# OSO-SAFE-C1-02.net
KiCad netlist of a schematic drawn in EAGLE
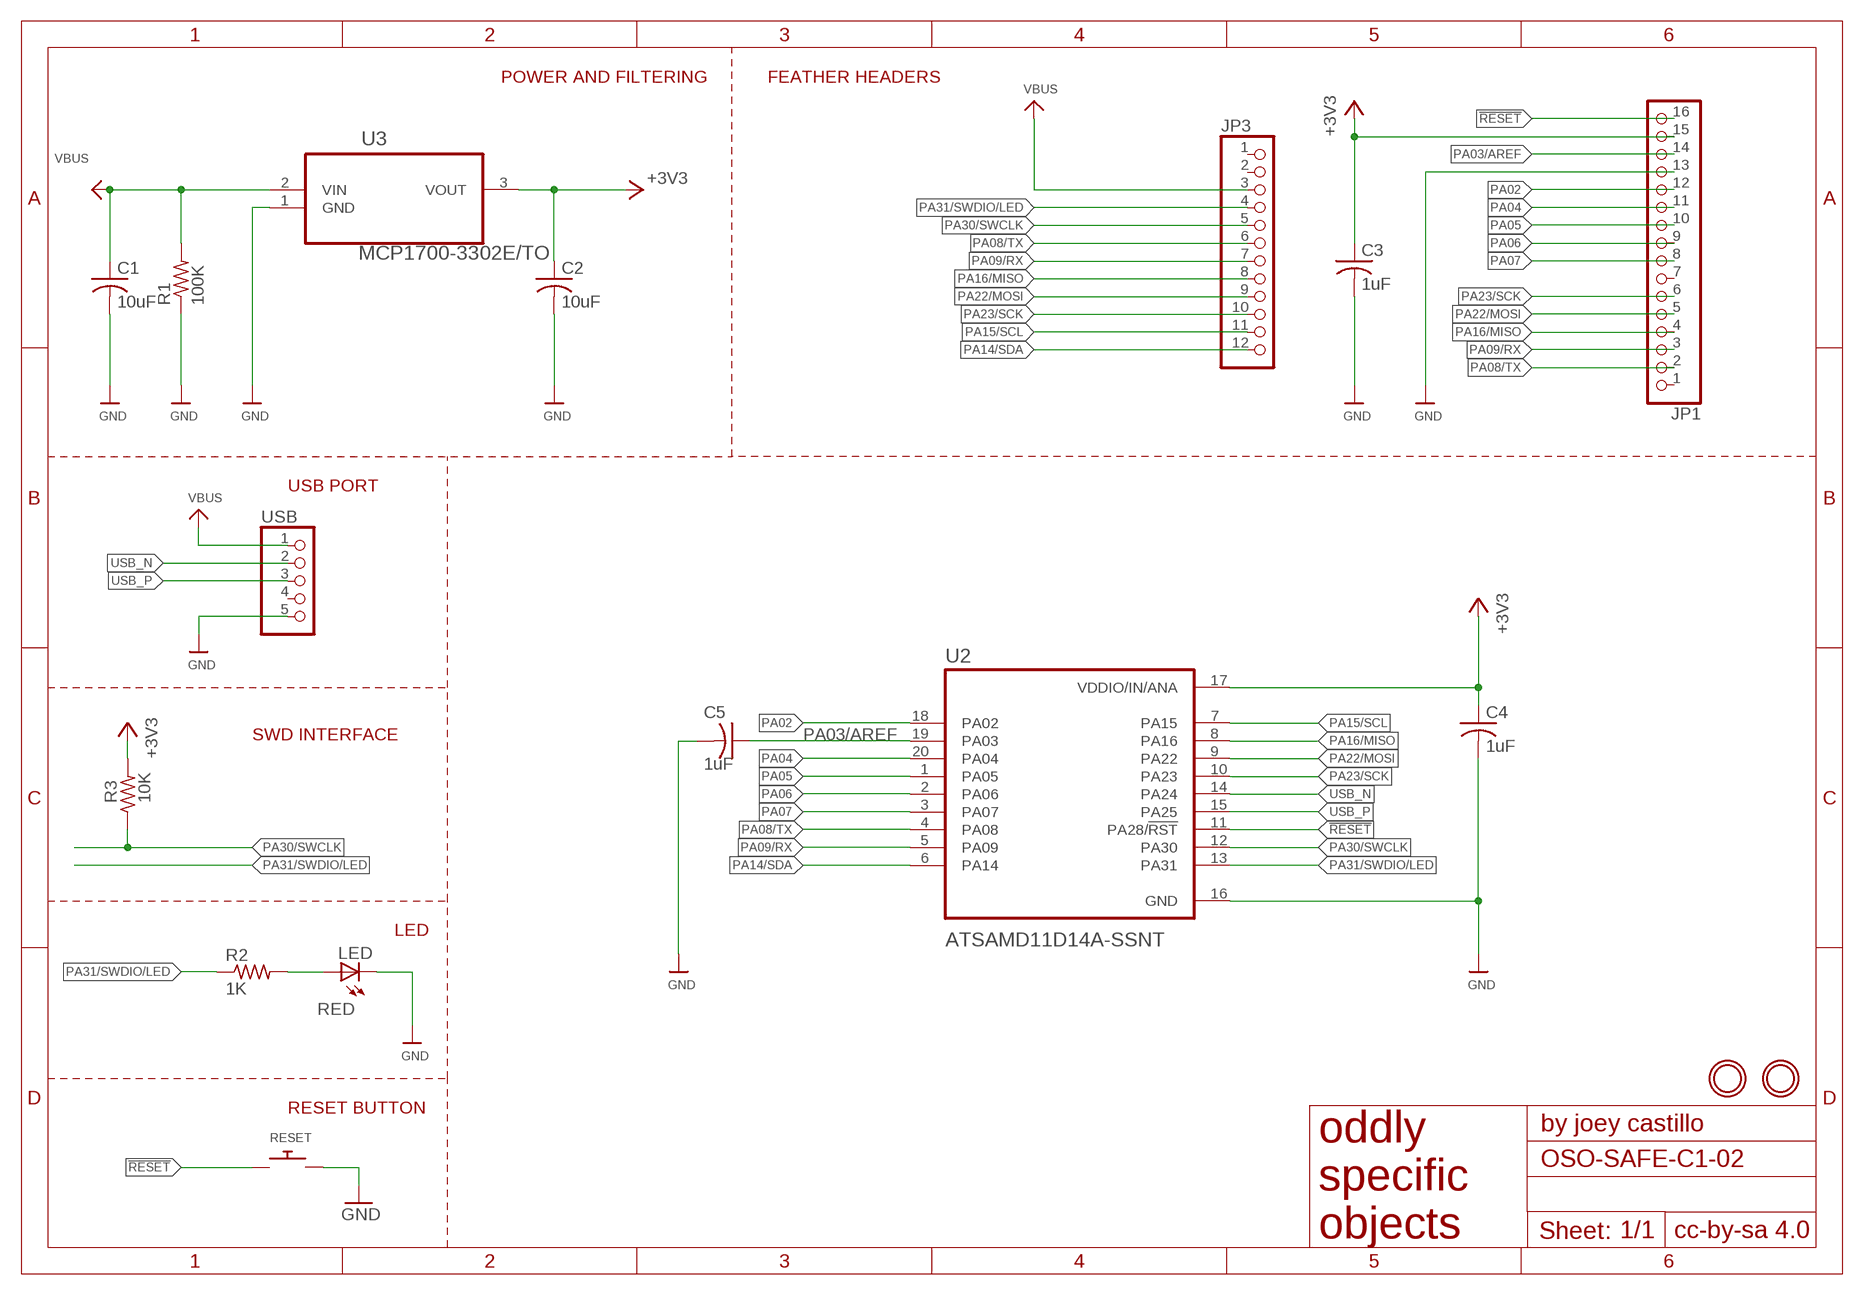
[diagram p0: schematic, sheet 1]

(export (version "E")
  (design (tool "Eeschema 10.0.6"))
  (components
    (comp (ref "C1")
      (value "10uF")
      (footprint "eagle-import:C050-025X075")
      (libsource (lib "eagle-import") (part "C-US050-025X075"))
    )
    (comp (ref "C2")
      (value "10uF")
      (footprint "eagle-import:C050-025X075")
      (libsource (lib "eagle-import") (part "C-US050-025X075"))
    )
    (comp (ref "C3")
      (value "1uF")
      (footprint "eagle-import:C025-025X050")
      (libsource (lib "eagle-import") (part "C-US025-025X050"))
    )
    (comp (ref "C4")
      (value "1uF")
      (footprint "eagle-import:C025-025X050")
      (libsource (lib "eagle-import") (part "C-US025-025X050"))
    )
    (comp (ref "C5")
      (value "1uF")
      (footprint "eagle-import:C025-025X050")
      (libsource (lib "eagle-import") (part "C-US025-025X050"))
    )
    (comp (ref "JP1")
      (value "HEADER-1X16_MIN")
      (footprint "eagle-import:1X16_ROUND_MIN")
      (libsource (lib "eagle-import") (part "HEADER-1X16_MIN"))
    )
    (comp (ref "JP3")
      (value "HEADER-1X12_MIN")
      (footprint "eagle-import:1X12_ROUND_MIN")
      (libsource (lib "eagle-import") (part "HEADER-1X12_MIN"))
    )
    (comp (ref "LED")
      (value "RED")
      (footprint "eagle-import:LED3MM")
      (libsource (lib "eagle-import") (part "LED3MM"))
    )
    (comp (ref "R1")
      (value "100K")
      (footprint "eagle-import:0207_9")
      (libsource (lib "eagle-import") (part "R-US_0207/9"))
    )
    (comp (ref "R2")
      (value "1K")
      (footprint "eagle-import:0207_9")
      (libsource (lib "eagle-import") (part "R-US_0207/9"))
    )
    (comp (ref "R3")
      (value "10K")
      (footprint "eagle-import:0207_9")
      (libsource (lib "eagle-import") (part "R-US_0207/9"))
    )
    (comp (ref "RESET")
      (value "SWITCH_PUSHBUTTONEVQ-PE")
      (footprint "eagle-import:TACT_PANA-EVQ")
      (libsource (lib "eagle-import") (part "SWITCH_PUSHBUTTONEVQ-PE"))
    )
    (comp (ref "U$10")
      (value "MOUNTINGHOLE2.5")
      (footprint "eagle-import:MOUNTINGHOLE_2.5_PLATED")
      (libsource (lib "eagle-import") (part "MOUNTINGHOLE2.5"))
    )
    (comp (ref "U$32")
      (value "MOUNTINGHOLE2.5")
      (footprint "eagle-import:MOUNTINGHOLE_2.5_PLATED")
      (libsource (lib "eagle-import") (part "MOUNTINGHOLE2.5"))
    )
    (comp (ref "U2")
      (value "ATSAMD11D14A-SSNT")
      (footprint "eagle-import:SOIC127P1030X265-20N")
      (fields (field (name "MF") "Microchip"))
      (libsource (lib "eagle-import") (part "ATSAMD11D14A-SSNT"))
    )
    (comp (ref "U3")
      (value "MCP1700-3302E/TO")
      (footprint "eagle-import:TO127P254X495-3")
      (fields (field (name "DIGI-KEY_PART_NUMBER") "MCP1700-3302E/TO-ND") (field (name "MF") "Microchip"))
      (libsource (lib "eagle-import") (part "MCP1700-3302E/TO"))
    )
    (comp (ref "USB")
      (value "PINHD-1X5")
      (footprint "eagle-import:1X05")
      (libsource (lib "eagle-import") (part "PINHD-1X5"))
    )
  )
  (nets
    (net (code "1") (name "+3V3") (class "Default")
      (node (ref "C2") (pin "1") (pinfunction "1_1") (pintype "passive"))
      (node (ref "C3") (pin "1") (pinfunction "1_1") (pintype "passive"))
      (node (ref "C4") (pin "1") (pinfunction "1_1") (pintype "passive"))
      (node (ref "JP1") (pin "15") (pinfunction "15_15") (pintype "passive"))
      (node (ref "R3") (pin "2") (pinfunction "2_2") (pintype "passive"))
      (node (ref "U2") (pin "17") (pinfunction "VDDIO/IN/ANA_17") (pintype "power_in"))
      (node (ref "U3") (pin "3") (pinfunction "VOUT_3") (pintype "output"))
    )
    (net (code "2") (name "/~{RESET}") (class "Default")
      (node (ref "JP1") (pin "16") (pinfunction "16_16") (pintype "passive"))
      (node (ref "RESET") (pin "P$1") (pinfunction "P$1_P$1") (pintype "passive"))
      (node (ref "U2") (pin "11") (pinfunction "PA28/~{RST}_11") (pintype "bidirectional"))
    )
    (net (code "3") (name "GND") (class "Default")
      (node (ref "C1") (pin "2") (pinfunction "2_2") (pintype "passive"))
      (node (ref "C2") (pin "2") (pinfunction "2_2") (pintype "passive"))
      (node (ref "C3") (pin "2") (pinfunction "2_2") (pintype "passive"))
      (node (ref "C4") (pin "2") (pinfunction "2_2") (pintype "passive"))
      (node (ref "C5") (pin "2") (pinfunction "2_2") (pintype "passive"))
      (node (ref "JP1") (pin "13") (pinfunction "13_13") (pintype "passive"))
      (node (ref "LED") (pin "K") (pinfunction "C_K") (pintype "passive"))
      (node (ref "R1") (pin "1") (pinfunction "1_1") (pintype "passive"))
      (node (ref "RESET") (pin "P$2") (pinfunction "P$2_P$2") (pintype "passive"))
      (node (ref "U2") (pin "16") (pinfunction "GND_16") (pintype "power_in"))
      (node (ref "U3") (pin "1") (pinfunction "GND_1") (pintype "passive"))
      (node (ref "USB") (pin "5") (pinfunction "5_5") (pintype "passive"))
    )
    (net (code "4") (name "Net-(LED-PadA)") (class "Default")
      (node (ref "LED") (pin "A") (pinfunction "A_A") (pintype "passive"))
      (node (ref "R2") (pin "2") (pinfunction "2_2") (pintype "passive"))
    )
    (net (code "5") (name "PA02") (class "Default")
      (node (ref "JP1") (pin "12") (pinfunction "12_12") (pintype "passive"))
      (node (ref "U2") (pin "18") (pinfunction "PA02_18") (pintype "bidirectional"))
    )
    (net (code "6") (name "PA03{slash}AREF") (class "Default")
      (node (ref "C5") (pin "1") (pinfunction "1_1") (pintype "passive"))
      (node (ref "JP1") (pin "14") (pinfunction "14_14") (pintype "passive"))
      (node (ref "U2") (pin "19") (pinfunction "PA03_19") (pintype "bidirectional"))
    )
    (net (code "7") (name "PA04") (class "Default")
      (node (ref "JP1") (pin "11") (pinfunction "11_11") (pintype "passive"))
      (node (ref "U2") (pin "20") (pinfunction "PA04_20") (pintype "bidirectional"))
    )
    (net (code "8") (name "PA05") (class "Default")
      (node (ref "JP1") (pin "10") (pinfunction "10_10") (pintype "passive"))
      (node (ref "U2") (pin "1") (pinfunction "PA05_1") (pintype "bidirectional"))
    )
    (net (code "9") (name "PA06") (class "Default")
      (node (ref "JP1") (pin "9") (pinfunction "9_9") (pintype "passive"))
      (node (ref "U2") (pin "2") (pinfunction "PA06_2") (pintype "bidirectional"))
    )
    (net (code "10") (name "PA07") (class "Default")
      (node (ref "JP1") (pin "8") (pinfunction "8_8") (pintype "passive"))
      (node (ref "U2") (pin "3") (pinfunction "PA07_3") (pintype "bidirectional"))
    )
    (net (code "11") (name "PA08{slash}TX") (class "Default")
      (node (ref "JP1") (pin "2") (pinfunction "2_2") (pintype "passive"))
      (node (ref "JP3") (pin "6") (pinfunction "6_6") (pintype "passive"))
      (node (ref "U2") (pin "4") (pinfunction "PA08_4") (pintype "bidirectional"))
    )
    (net (code "12") (name "PA09{slash}RX") (class "Default")
      (node (ref "JP1") (pin "3") (pinfunction "3_3") (pintype "passive"))
      (node (ref "JP3") (pin "7") (pinfunction "7_7") (pintype "passive"))
      (node (ref "U2") (pin "5") (pinfunction "PA09_5") (pintype "bidirectional"))
    )
    (net (code "13") (name "PA14{slash}SDA") (class "Default")
      (node (ref "JP3") (pin "12") (pinfunction "12_12") (pintype "passive"))
      (node (ref "U2") (pin "6") (pinfunction "PA14_6") (pintype "bidirectional"))
    )
    (net (code "14") (name "PA15{slash}SCL") (class "Default")
      (node (ref "JP3") (pin "11") (pinfunction "11_11") (pintype "passive"))
      (node (ref "U2") (pin "7") (pinfunction "PA15_7") (pintype "bidirectional"))
    )
    (net (code "15") (name "PA16{slash}MISO") (class "Default")
      (node (ref "JP1") (pin "4") (pinfunction "4_4") (pintype "passive"))
      (node (ref "JP3") (pin "8") (pinfunction "8_8") (pintype "passive"))
      (node (ref "U2") (pin "8") (pinfunction "PA16_8") (pintype "bidirectional"))
    )
    (net (code "16") (name "PA22{slash}MOSI") (class "Default")
      (node (ref "JP1") (pin "5") (pinfunction "5_5") (pintype "passive"))
      (node (ref "JP3") (pin "9") (pinfunction "9_9") (pintype "passive"))
      (node (ref "U2") (pin "9") (pinfunction "PA22_9") (pintype "bidirectional"))
    )
    (net (code "17") (name "PA23{slash}SCK") (class "Default")
      (node (ref "JP1") (pin "6") (pinfunction "6_6") (pintype "passive"))
      (node (ref "JP3") (pin "10") (pinfunction "10_10") (pintype "passive"))
      (node (ref "U2") (pin "10") (pinfunction "PA23_10") (pintype "bidirectional"))
    )
    (net (code "18") (name "PA30{slash}SWCLK") (class "Default")
      (node (ref "JP3") (pin "5") (pinfunction "5_5") (pintype "passive"))
      (node (ref "R3") (pin "1") (pinfunction "1_1") (pintype "passive"))
      (node (ref "U2") (pin "12") (pinfunction "PA30_12") (pintype "bidirectional"))
    )
    (net (code "19") (name "PA31{slash}SWDIO{slash}LED") (class "Default")
      (node (ref "JP3") (pin "4") (pinfunction "4_4") (pintype "passive"))
      (node (ref "R2") (pin "1") (pinfunction "1_1") (pintype "passive"))
      (node (ref "U2") (pin "13") (pinfunction "PA31_13") (pintype "bidirectional"))
    )
    (net (code "20") (name "USB_N") (class "Default")
      (node (ref "U2") (pin "14") (pinfunction "PA24_14") (pintype "bidirectional"))
      (node (ref "USB") (pin "2") (pinfunction "2_2") (pintype "passive"))
    )
    (net (code "21") (name "USB_P") (class "Default")
      (node (ref "U2") (pin "15") (pinfunction "PA25_15") (pintype "bidirectional"))
      (node (ref "USB") (pin "3") (pinfunction "3_3") (pintype "passive"))
    )
    (net (code "22") (name "VBUS") (class "Default")
      (node (ref "C1") (pin "1") (pinfunction "1_1") (pintype "passive"))
      (node (ref "JP3") (pin "3") (pinfunction "3_3") (pintype "passive"))
      (node (ref "R1") (pin "2") (pinfunction "2_2") (pintype "passive"))
      (node (ref "U3") (pin "2") (pinfunction "VIN_2") (pintype "input"))
      (node (ref "USB") (pin "1") (pinfunction "1_1") (pintype "passive"))
    )
    (net (code "23") (name "unconnected-(JP1-Pad1)") (class "Default")
      (node (ref "JP1") (pin "1") (pinfunction "1_1") (pintype "passive"))
    )
    (net (code "24") (name "unconnected-(JP1-Pad7)") (class "Default")
      (node (ref "JP1") (pin "7") (pinfunction "7_7") (pintype "passive"))
    )
    (net (code "25") (name "unconnected-(JP3-Pad1)") (class "Default")
      (node (ref "JP3") (pin "1") (pinfunction "1_1") (pintype "passive"))
    )
    (net (code "26") (name "unconnected-(JP3-Pad2)") (class "Default")
      (node (ref "JP3") (pin "2") (pinfunction "2_2") (pintype "passive"))
    )
    (net (code "27") (name "unconnected-(USB-Pad4)") (class "Default")
      (node (ref "USB") (pin "4") (pinfunction "4_4") (pintype "passive"))
    )
  )
)
